# DOG.net
KiCad netlist of a schematic drawn in Altium Designer
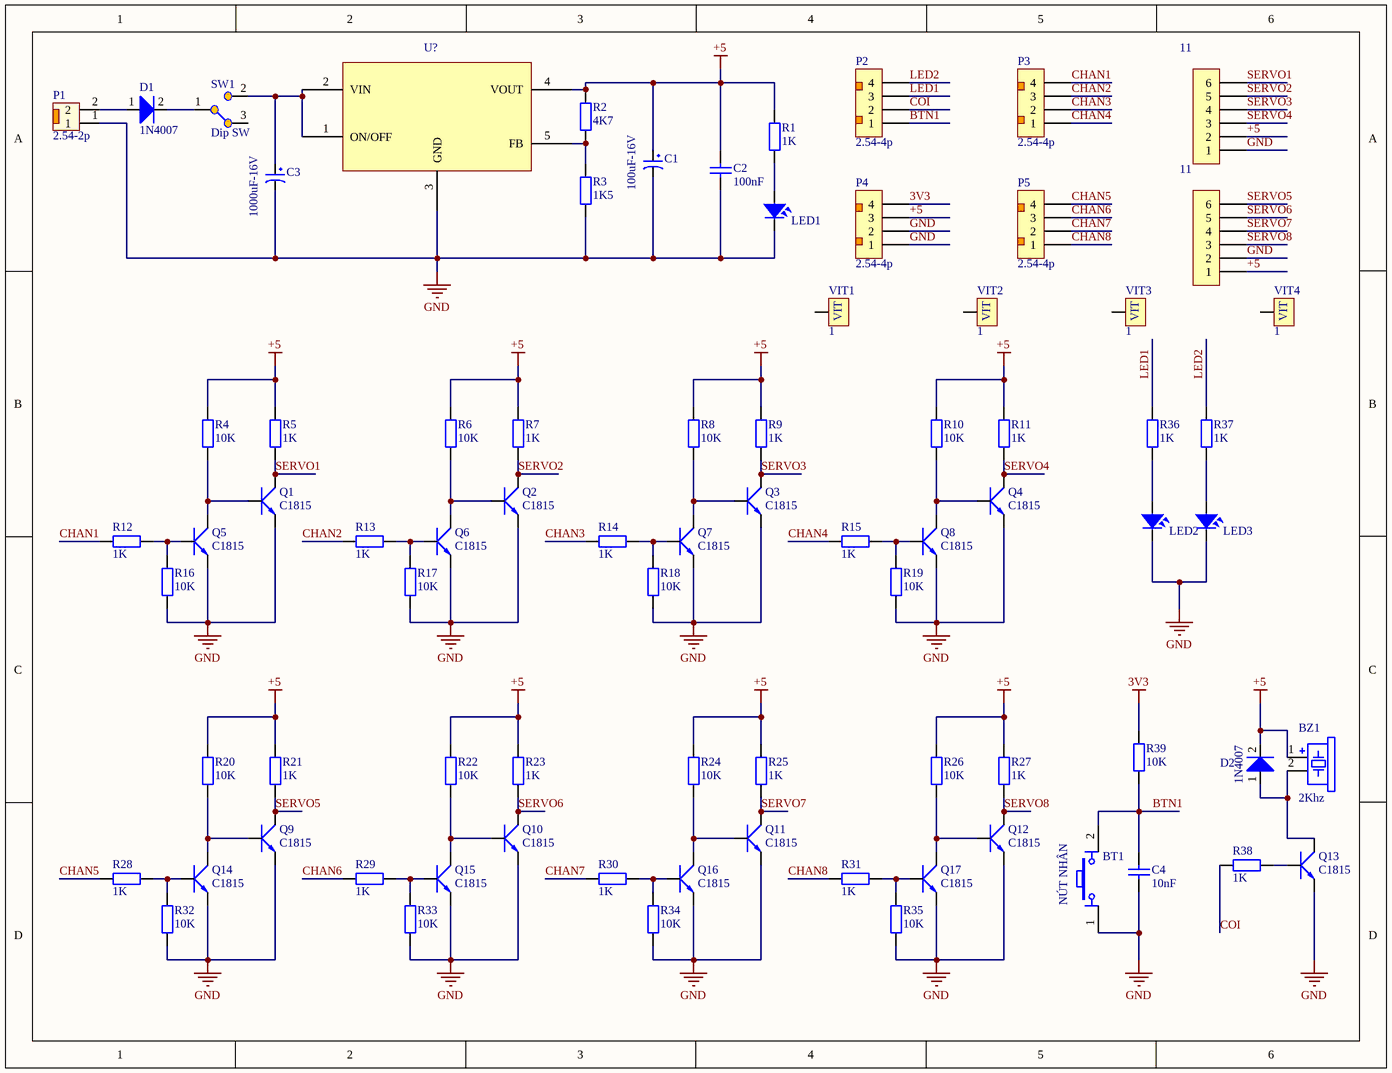
[diagram p0: DOG.SchDoc]

(export (version "E")
  (design (tool "Eeschema 10.0.6"))
  (components
    (comp (ref "BT1")
      (value "NÚT NHÂN")
      (footprint "Nut Nhan 4 Chan Cam 6x6")
      (description "Nut Nhan 4 Chan 6x6mm")
      (libsource (lib "Altium_Lib_by_KhueNguyenCreator") (part "Nut Nhan 4 Chan Cam 6x6"))
    )
    (comp (ref "BZ1")
      (value "2Khz")
      (footprint "coi xung")
      (description "Cắm")
      (libsource (lib "NhomLib") (part "Coi xung 2Khz"))
    )
    (comp (ref "C1")
      (value "100uF-16V")
      (footprint "tu hoa 5mm")
      (description "Cắm")
      (libsource (lib "NhomLib") (part "Tu Hoa 100uF 16V 5x7"))
    )
    (comp (ref "C2")
      (value "100nF")
      (footprint "tu gom")
      (description "Căm")
      (libsource (lib "NhomLib") (part "Tu gom 20pF 50V"))
    )
    (comp (ref "C3")
      (value "1000uF-16V")
      (footprint "tu hoa 8mm")
      (description "Cắm")
      (libsource (lib "NhomLib") (part "Tu Hoa 1000uF 16V 8x20"))
    )
    (comp (ref "C4")
      (value "10nF")
      (footprint "tu gom")
      (description "Căm")
      (libsource (lib "Altium_Lib_by_KhueNguyenCreator") (part "Tu gom 20pF 50V"))
    )
    (comp (ref "D1")
      (value "1N4007")
      (footprint "D5A")
      (description "Diode LS 1A 1000V DO-41")
      (libsource (lib "NhomLib") (part "1N4007"))
    )
    (comp (ref "D2")
      (value "1N4007")
      (footprint "1N4007")
      (description "Diode LS 1A 1000V DO-41")
      (libsource (lib "NhomLib") (part "1N4007"))
    )
    (comp (ref "H1")
      (value "11")
      (footprint "XH2.54M-6")
      (description "Cắm")
      (libsource (lib "Altium_Lib_by_KhueNguyenCreator") (part "Header 6P 2.54 Duc Thang"))
    )
    (comp (ref "H2")
      (value "11")
      (footprint "XH2.54M-6")
      (description "Cắm")
      (libsource (lib "Altium_Lib_by_KhueNguyenCreator") (part "Header 6P 2.54 Duc Thang"))
    )
    (comp (ref "LED1")
      (value "LED")
      (footprint "LED-5-RED")
      (description "LED Single colour Green and Red")
      (libsource (lib "NhomLib") (part "LED"))
    )
    (comp (ref "LED2")
      (value "LED")
      (footprint "LED-5-RED")
      (description "LED Single colour Green and Red")
      (libsource (lib "NhomLib") (part "LED"))
    )
    (comp (ref "LED3")
      (value "LED")
      (footprint "LED-5-Green")
      (description "LED Single colour Green and Red")
      (libsource (lib "NhomLib") (part "LED"))
    )
    (comp (ref "MIC1")
      (value "U?")
      (footprint "Mic5V")
      (description "3A")
      (libsource (lib "node_mcu") (part "Mic5V"))
    )
    (comp (ref "P1")
      (value "2.54-2p")
      (footprint "Header Duc Thang 2P 2.54")
      (description "Cắm")
      (libsource (lib "NhomLib") (part "Header 2.54-2p Duc Thang"))
    )
    (comp (ref "P2")
      (value "2.54-4p")
      (footprint "Header Duc Thang 4p 2.54")
      (description "Cắm")
      (libsource (lib "NhomLib") (part "Header 2.54_4p Duc Thang"))
    )
    (comp (ref "P3")
      (value "2.54-4p")
      (footprint "Header Duc Thang 4p 2.54")
      (description "Cắm")
      (libsource (lib "NhomLib") (part "Header 2.54_4p Duc Thang"))
    )
    (comp (ref "P4")
      (value "2.54-4p")
      (footprint "Header Duc Thang 4p 2.54")
      (description "Cắm")
      (libsource (lib "NhomLib") (part "Header 2.54_4p Duc Thang"))
    )
    (comp (ref "P5")
      (value "2.54-4p")
      (footprint "Header Duc Thang 4p 2.54")
      (description "Cắm")
      (libsource (lib "NhomLib") (part "Header 2.54_4p Duc Thang"))
    )
    (comp (ref "Q1")
      (value "C1815")
      (footprint "QTO-92")
      (description "NPN 600mW, ECB")
      (libsource (lib "syhaunguyen") (part "C1815"))
    )
    (comp (ref "Q2")
      (value "C1815")
      (footprint "QTO-92")
      (description "NPN 600mW, ECB")
      (libsource (lib "syhaunguyen") (part "C1815"))
    )
    (comp (ref "Q3")
      (value "C1815")
      (footprint "QTO-92")
      (description "NPN 600mW, ECB")
      (libsource (lib "syhaunguyen") (part "C1815"))
    )
    (comp (ref "Q4")
      (value "C1815")
      (footprint "QTO-92")
      (description "NPN 600mW, ECB")
      (libsource (lib "syhaunguyen") (part "C1815"))
    )
    (comp (ref "Q5")
      (value "C1815")
      (footprint "QTO-92")
      (description "NPN 600mW, ECB")
      (libsource (lib "syhaunguyen") (part "C1815"))
    )
    (comp (ref "Q6")
      (value "C1815")
      (footprint "QTO-92")
      (description "NPN 600mW, ECB")
      (libsource (lib "syhaunguyen") (part "C1815"))
    )
    (comp (ref "Q7")
      (value "C1815")
      (footprint "QTO-92")
      (description "NPN 600mW, ECB")
      (libsource (lib "syhaunguyen") (part "C1815"))
    )
    (comp (ref "Q8")
      (value "C1815")
      (footprint "QTO-92")
      (description "NPN 600mW, ECB")
      (libsource (lib "syhaunguyen") (part "C1815"))
    )
    (comp (ref "Q9")
      (value "C1815")
      (footprint "QTO-92")
      (description "NPN 600mW, ECB")
      (libsource (lib "syhaunguyen") (part "C1815"))
    )
    (comp (ref "Q10")
      (value "C1815")
      (footprint "QTO-92")
      (description "NPN 600mW, ECB")
      (libsource (lib "syhaunguyen") (part "C1815"))
    )
    (comp (ref "Q11")
      (value "C1815")
      (footprint "QTO-92")
      (description "NPN 600mW, ECB")
      (libsource (lib "syhaunguyen") (part "C1815"))
    )
    (comp (ref "Q12")
      (value "C1815")
      (footprint "QTO-92")
      (description "NPN 600mW, ECB")
      (libsource (lib "syhaunguyen") (part "C1815"))
    )
    (comp (ref "Q13")
      (value "C1815")
      (footprint "QTO-92")
      (description "NPN 600mW, ECB")
      (libsource (lib "syhaunguyen") (part "C1815"))
    )
    (comp (ref "Q14")
      (value "C1815")
      (footprint "QTO-92")
      (description "NPN 600mW, ECB")
      (libsource (lib "syhaunguyen") (part "C1815"))
    )
    (comp (ref "Q15")
      (value "C1815")
      (footprint "QTO-92")
      (description "NPN 600mW, ECB")
      (libsource (lib "syhaunguyen") (part "C1815"))
    )
    (comp (ref "Q16")
      (value "C1815")
      (footprint "QTO-92")
      (description "NPN 600mW, ECB")
      (libsource (lib "syhaunguyen") (part "C1815"))
    )
    (comp (ref "Q17")
      (value "C1815")
      (footprint "QTO-92")
      (description "NPN 600mW, ECB")
      (libsource (lib "syhaunguyen") (part "C1815"))
    )
    (comp (ref "R1")
      (value "1K")
      (footprint "tro vach 1/4w")
      (description "Cắm")
      (libsource (lib "NhomLib") (part "Tro Vach 1/4W 5% 1k"))
    )
    (comp (ref "R2")
      (value "4K7")
      (footprint "tro vach 1/4w")
      (description "Cắm")
      (libsource (lib "NhomLib") (part "Tro Vach 1/4W 5% 1k"))
    )
    (comp (ref "R3")
      (value "1K5")
      (footprint "tro vach 1/4w")
      (description "Cắm")
      (libsource (lib "NhomLib") (part "Tro Vach 1/4W 5% 1k"))
    )
    (comp (ref "R4")
      (value "10K")
      (footprint "tro vach 1/4w")
      (description "Cắm")
      (libsource (lib "NhomLib") (part "Tro Vach 1/4W 5% 1k"))
    )
    (comp (ref "R5")
      (value "1K")
      (footprint "tro vach 1/4w")
      (description "Cắm")
      (libsource (lib "NhomLib") (part "Tro Vach 1/4W 5% 1k"))
    )
    (comp (ref "R6")
      (value "10K")
      (footprint "tro vach 1/4w")
      (description "Cắm")
      (libsource (lib "NhomLib") (part "Tro Vach 1/4W 5% 1k"))
    )
    (comp (ref "R7")
      (value "1K")
      (footprint "tro vach 1/4w")
      (description "Cắm")
      (libsource (lib "NhomLib") (part "Tro Vach 1/4W 5% 1k"))
    )
    (comp (ref "R8")
      (value "10K")
      (footprint "tro vach 1/4w")
      (description "Cắm")
      (libsource (lib "NhomLib") (part "Tro Vach 1/4W 5% 1k"))
    )
    (comp (ref "R9")
      (value "1K")
      (footprint "tro vach 1/4w")
      (description "Cắm")
      (libsource (lib "NhomLib") (part "Tro Vach 1/4W 5% 1k"))
    )
    (comp (ref "R10")
      (value "10K")
      (footprint "tro vach 1/4w")
      (description "Cắm")
      (libsource (lib "NhomLib") (part "Tro Vach 1/4W 5% 1k"))
    )
    (comp (ref "R11")
      (value "1K")
      (footprint "tro vach 1/4w")
      (description "Cắm")
      (libsource (lib "NhomLib") (part "Tro Vach 1/4W 5% 1k"))
    )
    (comp (ref "R12")
      (value "1K")
      (footprint "tro vach 1/4w")
      (description "Cắm")
      (libsource (lib "NhomLib") (part "Tro Vach 1/4W 5% 1k"))
    )
    (comp (ref "R13")
      (value "1K")
      (footprint "tro vach 1/4w")
      (description "Cắm")
      (libsource (lib "NhomLib") (part "Tro Vach 1/4W 5% 1k"))
    )
    (comp (ref "R14")
      (value "1K")
      (footprint "tro vach 1/4w")
      (description "Cắm")
      (libsource (lib "NhomLib") (part "Tro Vach 1/4W 5% 1k"))
    )
    (comp (ref "R15")
      (value "1K")
      (footprint "tro vach 1/4w")
      (description "Cắm")
      (libsource (lib "NhomLib") (part "Tro Vach 1/4W 5% 1k"))
    )
    (comp (ref "R16")
      (value "10K")
      (footprint "tro vach 1/4w")
      (description "Cắm")
      (libsource (lib "NhomLib") (part "Tro Vach 1/4W 5% 1k"))
    )
    (comp (ref "R17")
      (value "10K")
      (footprint "tro vach 1/4w")
      (description "Cắm")
      (libsource (lib "NhomLib") (part "Tro Vach 1/4W 5% 1k"))
    )
    (comp (ref "R18")
      (value "10K")
      (footprint "tro vach 1/4w")
      (description "Cắm")
      (libsource (lib "NhomLib") (part "Tro Vach 1/4W 5% 1k"))
    )
    (comp (ref "R19")
      (value "10K")
      (footprint "tro vach 1/4w")
      (description "Cắm")
      (libsource (lib "NhomLib") (part "Tro Vach 1/4W 5% 1k"))
    )
    (comp (ref "R20")
      (value "10K")
      (footprint "tro vach 1/4w")
      (description "Cắm")
      (libsource (lib "NhomLib") (part "Tro Vach 1/4W 5% 1k"))
    )
    (comp (ref "R21")
      (value "1K")
      (footprint "tro vach 1/4w")
      (description "Cắm")
      (libsource (lib "NhomLib") (part "Tro Vach 1/4W 5% 1k"))
    )
    (comp (ref "R22")
      (value "10K")
      (footprint "tro vach 1/4w")
      (description "Cắm")
      (libsource (lib "NhomLib") (part "Tro Vach 1/4W 5% 1k"))
    )
    (comp (ref "R23")
      (value "1K")
      (footprint "tro vach 1/4w")
      (description "Cắm")
      (libsource (lib "NhomLib") (part "Tro Vach 1/4W 5% 1k"))
    )
    (comp (ref "R24")
      (value "10K")
      (footprint "tro vach 1/4w")
      (description "Cắm")
      (libsource (lib "NhomLib") (part "Tro Vach 1/4W 5% 1k"))
    )
    (comp (ref "R25")
      (value "1K")
      (footprint "tro vach 1/4w")
      (description "Cắm")
      (libsource (lib "NhomLib") (part "Tro Vach 1/4W 5% 1k"))
    )
    (comp (ref "R26")
      (value "10K")
      (footprint "tro vach 1/4w")
      (description "Cắm")
      (libsource (lib "NhomLib") (part "Tro Vach 1/4W 5% 1k"))
    )
    (comp (ref "R27")
      (value "1K")
      (footprint "tro vach 1/4w")
      (description "Cắm")
      (libsource (lib "NhomLib") (part "Tro Vach 1/4W 5% 1k"))
    )
    (comp (ref "R28")
      (value "1K")
      (footprint "tro vach 1/4w")
      (description "Cắm")
      (libsource (lib "NhomLib") (part "Tro Vach 1/4W 5% 1k"))
    )
    (comp (ref "R29")
      (value "1K")
      (footprint "tro vach 1/4w")
      (description "Cắm")
      (libsource (lib "NhomLib") (part "Tro Vach 1/4W 5% 1k"))
    )
    (comp (ref "R30")
      (value "1K")
      (footprint "tro vach 1/4w")
      (description "Cắm")
      (libsource (lib "NhomLib") (part "Tro Vach 1/4W 5% 1k"))
    )
    (comp (ref "R31")
      (value "1K")
      (footprint "tro vach 1/4w")
      (description "Cắm")
      (libsource (lib "NhomLib") (part "Tro Vach 1/4W 5% 1k"))
    )
    (comp (ref "R32")
      (value "10K")
      (footprint "tro vach 1/4w")
      (description "Cắm")
      (libsource (lib "NhomLib") (part "Tro Vach 1/4W 5% 1k"))
    )
    (comp (ref "R33")
      (value "10K")
      (footprint "tro vach 1/4w")
      (description "Cắm")
      (libsource (lib "NhomLib") (part "Tro Vach 1/4W 5% 1k"))
    )
    (comp (ref "R34")
      (value "10K")
      (footprint "tro vach 1/4w")
      (description "Cắm")
      (libsource (lib "NhomLib") (part "Tro Vach 1/4W 5% 1k"))
    )
    (comp (ref "R35")
      (value "10K")
      (footprint "tro vach 1/4w")
      (description "Cắm")
      (libsource (lib "NhomLib") (part "Tro Vach 1/4W 5% 1k"))
    )
    (comp (ref "R36")
      (value "1K")
      (footprint "tro vach 1/4w")
      (description "Cắm")
      (libsource (lib "NhomLib") (part "Tro Vach 1/4W 5% 1k"))
    )
    (comp (ref "R37")
      (value "1K")
      (footprint "tro vach 1/4w")
      (description "Cắm")
      (libsource (lib "NhomLib") (part "Tro Vach 1/4W 5% 1k"))
    )
    (comp (ref "R38")
      (value "1K")
      (footprint "tro vach 1/4w")
      (description "Cắm")
      (libsource (lib "NhomLib") (part "Tro Vach 1/4W 5% 1k"))
    )
    (comp (ref "R39")
      (value "10K")
      (footprint "tro vach 1/4w")
      (description "Cắm")
      (libsource (lib "NhomLib") (part "Tro Vach 1/4W 5% 1k"))
    )
    (comp (ref "SW1")
      (value "Dip SW")
      (footprint "SW3P")
      (description "Dip Switch 3 pin")
      (libsource (lib "VPMyLibrary") (part "Switch3P"))
    )
    (comp (ref "VIT1")
      (value "1")
      (footprint "VIT")
      (description "Oc Vit")
      (libsource (lib "NhomLib") (part "VIT"))
    )
    (comp (ref "VIT2")
      (value "1")
      (footprint "VIT")
      (description "Oc Vit")
      (libsource (lib "NhomLib") (part "VIT"))
    )
    (comp (ref "VIT3")
      (value "1")
      (footprint "VIT")
      (description "Oc Vit")
      (libsource (lib "NhomLib") (part "VIT"))
    )
    (comp (ref "VIT4")
      (value "1")
      (footprint "VIT")
      (description "Oc Vit")
      (libsource (lib "NhomLib") (part "VIT"))
    )
  )
  (nets
    (net (code "1") (name "+5") (class "Default")
      (node (ref "BZ1") (pin "1") (pinfunction "1_1") (pintype "passive"))
      (node (ref "C1") (pin "1") (pinfunction "1_1") (pintype "passive"))
      (node (ref "C2") (pin "1") (pinfunction "1_1") (pintype "passive"))
      (node (ref "D2") (pin "2") (pinfunction "K_2") (pintype "passive"))
      (node (ref "H1") (pin "2") (pinfunction "2_2") (pintype "passive"))
      (node (ref "H2") (pin "1") (pinfunction "1_1") (pintype "passive"))
      (node (ref "MIC1") (pin "4") (pinfunction "VOUT_4") (pintype "passive"))
      (node (ref "P4") (pin "3") (pinfunction "3_3") (pintype "passive"))
      (node (ref "R1") (pin "1") (pinfunction "1_1") (pintype "passive"))
      (node (ref "R10") (pin "2") (pinfunction "2_2") (pintype "passive"))
      (node (ref "R11") (pin "2") (pinfunction "2_2") (pintype "passive"))
      (node (ref "R2") (pin "2") (pinfunction "2_2") (pintype "passive"))
      (node (ref "R20") (pin "2") (pinfunction "2_2") (pintype "passive"))
      (node (ref "R21") (pin "2") (pinfunction "2_2") (pintype "passive"))
      (node (ref "R22") (pin "2") (pinfunction "2_2") (pintype "passive"))
      (node (ref "R23") (pin "2") (pinfunction "2_2") (pintype "passive"))
      (node (ref "R24") (pin "2") (pinfunction "2_2") (pintype "passive"))
      (node (ref "R25") (pin "2") (pinfunction "2_2") (pintype "passive"))
      (node (ref "R26") (pin "2") (pinfunction "2_2") (pintype "passive"))
      (node (ref "R27") (pin "2") (pinfunction "2_2") (pintype "passive"))
      (node (ref "R4") (pin "2") (pinfunction "2_2") (pintype "passive"))
      (node (ref "R5") (pin "2") (pinfunction "2_2") (pintype "passive"))
      (node (ref "R6") (pin "2") (pinfunction "2_2") (pintype "passive"))
      (node (ref "R7") (pin "2") (pinfunction "2_2") (pintype "passive"))
      (node (ref "R8") (pin "2") (pinfunction "2_2") (pintype "passive"))
      (node (ref "R9") (pin "2") (pinfunction "2_2") (pintype "passive"))
    )
    (net (code "2") (name "/BTN1") (class "Default")
      (node (ref "BT1") (pin "2") (pintype "passive"))
      (node (ref "C4") (pin "1") (pinfunction "1_1") (pintype "passive"))
      (node (ref "P2") (pin "1") (pinfunction "1_1") (pintype "passive"))
      (node (ref "R39") (pin "1") (pinfunction "1_1") (pintype "passive"))
    )
    (net (code "3") (name "/CHAN1") (class "Default")
      (node (ref "P3") (pin "4") (pinfunction "4_4") (pintype "passive"))
      (node (ref "R12") (pin "2") (pinfunction "2_2") (pintype "passive"))
    )
    (net (code "4") (name "/CHAN2") (class "Default")
      (node (ref "P3") (pin "3") (pinfunction "3_3") (pintype "passive"))
      (node (ref "R13") (pin "2") (pinfunction "2_2") (pintype "passive"))
    )
    (net (code "5") (name "/CHAN3") (class "Default")
      (node (ref "P3") (pin "2") (pinfunction "2_2") (pintype "passive"))
      (node (ref "R14") (pin "2") (pinfunction "2_2") (pintype "passive"))
    )
    (net (code "6") (name "/CHAN4") (class "Default")
      (node (ref "P3") (pin "1") (pinfunction "1_1") (pintype "passive"))
      (node (ref "R15") (pin "2") (pinfunction "2_2") (pintype "passive"))
    )
    (net (code "7") (name "/CHAN5") (class "Default")
      (node (ref "P5") (pin "4") (pinfunction "4_4") (pintype "passive"))
      (node (ref "R28") (pin "2") (pinfunction "2_2") (pintype "passive"))
    )
    (net (code "8") (name "/CHAN6") (class "Default")
      (node (ref "P5") (pin "3") (pinfunction "3_3") (pintype "passive"))
      (node (ref "R29") (pin "2") (pinfunction "2_2") (pintype "passive"))
    )
    (net (code "9") (name "/CHAN7") (class "Default")
      (node (ref "P5") (pin "2") (pinfunction "2_2") (pintype "passive"))
      (node (ref "R30") (pin "2") (pinfunction "2_2") (pintype "passive"))
    )
    (net (code "10") (name "/CHAN8") (class "Default")
      (node (ref "P5") (pin "1") (pinfunction "1_1") (pintype "passive"))
      (node (ref "R31") (pin "2") (pinfunction "2_2") (pintype "passive"))
    )
    (net (code "11") (name "/COI") (class "Default")
      (node (ref "P2") (pin "2") (pinfunction "2_2") (pintype "passive"))
      (node (ref "R38") (pin "2") (pinfunction "2_2") (pintype "passive"))
    )
    (net (code "12") (name "/LED1") (class "Default")
      (node (ref "P2") (pin "3") (pinfunction "3_3") (pintype "passive"))
      (node (ref "R36") (pin "1") (pinfunction "1_1") (pintype "passive"))
    )
    (net (code "13") (name "/LED2") (class "Default")
      (node (ref "P2") (pin "4") (pinfunction "4_4") (pintype "passive"))
      (node (ref "R37") (pin "1") (pinfunction "1_1") (pintype "passive"))
    )
    (net (code "14") (name "/SERVO1") (class "Default")
      (node (ref "H1") (pin "6") (pinfunction "6_6") (pintype "passive"))
      (node (ref "Q1") (pin "2") (pinfunction "C_2") (pintype "passive"))
      (node (ref "R5") (pin "1") (pinfunction "1_1") (pintype "passive"))
    )
    (net (code "15") (name "/SERVO2") (class "Default")
      (node (ref "H1") (pin "5") (pinfunction "5_5") (pintype "passive"))
      (node (ref "Q2") (pin "2") (pinfunction "C_2") (pintype "passive"))
      (node (ref "R7") (pin "1") (pinfunction "1_1") (pintype "passive"))
    )
    (net (code "16") (name "/SERVO3") (class "Default")
      (node (ref "H1") (pin "4") (pinfunction "4_4") (pintype "passive"))
      (node (ref "Q3") (pin "2") (pinfunction "C_2") (pintype "passive"))
      (node (ref "R9") (pin "1") (pinfunction "1_1") (pintype "passive"))
    )
    (net (code "17") (name "/SERVO4") (class "Default")
      (node (ref "H1") (pin "3") (pinfunction "3_3") (pintype "passive"))
      (node (ref "Q4") (pin "2") (pinfunction "C_2") (pintype "passive"))
      (node (ref "R11") (pin "1") (pinfunction "1_1") (pintype "passive"))
    )
    (net (code "18") (name "/SERVO5") (class "Default")
      (node (ref "H2") (pin "6") (pinfunction "6_6") (pintype "passive"))
      (node (ref "Q9") (pin "2") (pinfunction "C_2") (pintype "passive"))
      (node (ref "R21") (pin "1") (pinfunction "1_1") (pintype "passive"))
    )
    (net (code "19") (name "/SERVO6") (class "Default")
      (node (ref "H2") (pin "5") (pinfunction "5_5") (pintype "passive"))
      (node (ref "Q10") (pin "2") (pinfunction "C_2") (pintype "passive"))
      (node (ref "R23") (pin "1") (pinfunction "1_1") (pintype "passive"))
    )
    (net (code "20") (name "/SERVO7") (class "Default")
      (node (ref "H2") (pin "4") (pinfunction "4_4") (pintype "passive"))
      (node (ref "Q11") (pin "2") (pinfunction "C_2") (pintype "passive"))
      (node (ref "R25") (pin "1") (pinfunction "1_1") (pintype "passive"))
    )
    (net (code "21") (name "/SERVO8") (class "Default")
      (node (ref "H2") (pin "3") (pinfunction "3_3") (pintype "passive"))
      (node (ref "Q12") (pin "2") (pinfunction "C_2") (pintype "passive"))
      (node (ref "R27") (pin "1") (pinfunction "1_1") (pintype "passive"))
    )
    (net (code "22") (name "3V3") (class "Default")
      (node (ref "P4") (pin "4") (pinfunction "4_4") (pintype "passive"))
      (node (ref "R39") (pin "2") (pinfunction "2_2") (pintype "passive"))
    )
    (net (code "23") (name "GND") (class "Default")
      (node (ref "BT1") (pin "1") (pintype "passive"))
      (node (ref "C1") (pin "2") (pinfunction "2_2") (pintype "passive"))
      (node (ref "C2") (pin "2") (pinfunction "2_2") (pintype "passive"))
      (node (ref "C3") (pin "2") (pinfunction "2_2") (pintype "passive"))
      (node (ref "C4") (pin "2") (pinfunction "2_2") (pintype "passive"))
      (node (ref "H1") (pin "1") (pinfunction "1_1") (pintype "passive"))
      (node (ref "H2") (pin "2") (pinfunction "2_2") (pintype "passive"))
      (node (ref "LED1") (pin "2") (pinfunction "2_2") (pintype "passive"))
      (node (ref "LED2") (pin "2") (pinfunction "2_2") (pintype "passive"))
      (node (ref "LED3") (pin "2") (pinfunction "2_2") (pintype "passive"))
      (node (ref "MIC1") (pin "3") (pinfunction "GND_3") (pintype "passive"))
      (node (ref "P1") (pin "1") (pinfunction "1_1") (pintype "passive"))
      (node (ref "P4") (pin "1") (pinfunction "1_1") (pintype "passive"))
      (node (ref "P4") (pin "2") (pinfunction "2_2") (pintype "passive"))
      (node (ref "Q1") (pin "1") (pinfunction "E_1") (pintype "passive"))
      (node (ref "Q10") (pin "1") (pinfunction "E_1") (pintype "passive"))
      (node (ref "Q11") (pin "1") (pinfunction "E_1") (pintype "passive"))
      (node (ref "Q12") (pin "1") (pinfunction "E_1") (pintype "passive"))
      (node (ref "Q13") (pin "1") (pinfunction "E_1") (pintype "passive"))
      (node (ref "Q14") (pin "1") (pinfunction "E_1") (pintype "passive"))
      (node (ref "Q15") (pin "1") (pinfunction "E_1") (pintype "passive"))
      (node (ref "Q16") (pin "1") (pinfunction "E_1") (pintype "passive"))
      (node (ref "Q17") (pin "1") (pinfunction "E_1") (pintype "passive"))
      (node (ref "Q2") (pin "1") (pinfunction "E_1") (pintype "passive"))
      (node (ref "Q3") (pin "1") (pinfunction "E_1") (pintype "passive"))
      (node (ref "Q4") (pin "1") (pinfunction "E_1") (pintype "passive"))
      (node (ref "Q5") (pin "1") (pinfunction "E_1") (pintype "passive"))
      (node (ref "Q6") (pin "1") (pinfunction "E_1") (pintype "passive"))
      (node (ref "Q7") (pin "1") (pinfunction "E_1") (pintype "passive"))
      (node (ref "Q8") (pin "1") (pinfunction "E_1") (pintype "passive"))
      (node (ref "Q9") (pin "1") (pinfunction "E_1") (pintype "passive"))
      (node (ref "R16") (pin "1") (pinfunction "1_1") (pintype "passive"))
      (node (ref "R17") (pin "1") (pinfunction "1_1") (pintype "passive"))
      (node (ref "R18") (pin "1") (pinfunction "1_1") (pintype "passive"))
      (node (ref "R19") (pin "1") (pinfunction "1_1") (pintype "passive"))
      (node (ref "R3") (pin "1") (pinfunction "1_1") (pintype "passive"))
      (node (ref "R32") (pin "1") (pinfunction "1_1") (pintype "passive"))
      (node (ref "R33") (pin "1") (pinfunction "1_1") (pintype "passive"))
      (node (ref "R34") (pin "1") (pinfunction "1_1") (pintype "passive"))
      (node (ref "R35") (pin "1") (pinfunction "1_1") (pintype "passive"))
    )
    (net (code "24") (name "Net-(D1-A)") (class "Default")
      (node (ref "D1") (pin "1") (pinfunction "A_1") (pintype "passive"))
      (node (ref "P1") (pin "2") (pinfunction "2_2") (pintype "passive"))
    )
    (net (code "25") (name "Net-(D1-K)") (class "Default")
      (node (ref "D1") (pin "2") (pinfunction "K_2") (pintype "passive"))
      (node (ref "SW1") (pin "1") (pinfunction "COM_1") (pintype "passive"))
    )
    (net (code "26") (name "Net-(D2-A)") (class "Default")
      (node (ref "BZ1") (pin "2") (pinfunction "2_2") (pintype "passive"))
      (node (ref "D2") (pin "1") (pinfunction "A_1") (pintype "passive"))
      (node (ref "Q13") (pin "2") (pinfunction "C_2") (pintype "passive"))
    )
    (net (code "27") (name "Net-(LED1-Pad1)") (class "Default")
      (node (ref "LED1") (pin "1") (pinfunction "1_1") (pintype "passive"))
      (node (ref "R1") (pin "2") (pinfunction "2_2") (pintype "passive"))
    )
    (net (code "28") (name "Net-(LED2-Pad1)") (class "Default")
      (node (ref "LED2") (pin "1") (pinfunction "1_1") (pintype "passive"))
      (node (ref "R36") (pin "2") (pinfunction "2_2") (pintype "passive"))
    )
    (net (code "29") (name "Net-(LED3-Pad1)") (class "Default")
      (node (ref "LED3") (pin "1") (pinfunction "1_1") (pintype "passive"))
      (node (ref "R37") (pin "2") (pinfunction "2_2") (pintype "passive"))
    )
    (net (code "30") (name "Net-(MIC1-FB)") (class "Default")
      (node (ref "MIC1") (pin "5") (pinfunction "FB_5") (pintype "passive"))
      (node (ref "R2") (pin "1") (pinfunction "1_1") (pintype "passive"))
      (node (ref "R3") (pin "2") (pinfunction "2_2") (pintype "passive"))
    )
    (net (code "31") (name "Net-(MIC1-ON{slash}OFF)") (class "Default")
      (node (ref "C3") (pin "1") (pinfunction "1_1") (pintype "passive"))
      (node (ref "MIC1") (pin "1") (pinfunction "ON/OFF_1") (pintype "passive"))
      (node (ref "MIC1") (pin "2") (pinfunction "VIN_2") (pintype "passive"))
      (node (ref "SW1") (pin "2") (pinfunction "NC_2") (pintype "passive"))
    )
    (net (code "32") (name "Net-(Q1-B)") (class "Default")
      (node (ref "Q1") (pin "3") (pinfunction "B_3") (pintype "passive"))
      (node (ref "Q5") (pin "2") (pinfunction "C_2") (pintype "passive"))
      (node (ref "R4") (pin "1") (pinfunction "1_1") (pintype "passive"))
    )
    (net (code "33") (name "Net-(Q2-B)") (class "Default")
      (node (ref "Q2") (pin "3") (pinfunction "B_3") (pintype "passive"))
      (node (ref "Q6") (pin "2") (pinfunction "C_2") (pintype "passive"))
      (node (ref "R6") (pin "1") (pinfunction "1_1") (pintype "passive"))
    )
    (net (code "34") (name "Net-(Q3-B)") (class "Default")
      (node (ref "Q3") (pin "3") (pinfunction "B_3") (pintype "passive"))
      (node (ref "Q7") (pin "2") (pinfunction "C_2") (pintype "passive"))
      (node (ref "R8") (pin "1") (pinfunction "1_1") (pintype "passive"))
    )
    (net (code "35") (name "Net-(Q4-B)") (class "Default")
      (node (ref "Q4") (pin "3") (pinfunction "B_3") (pintype "passive"))
      (node (ref "Q8") (pin "2") (pinfunction "C_2") (pintype "passive"))
      (node (ref "R10") (pin "1") (pinfunction "1_1") (pintype "passive"))
    )
    (net (code "36") (name "Net-(Q5-B)") (class "Default")
      (node (ref "Q5") (pin "3") (pinfunction "B_3") (pintype "passive"))
      (node (ref "R12") (pin "1") (pinfunction "1_1") (pintype "passive"))
      (node (ref "R16") (pin "2") (pinfunction "2_2") (pintype "passive"))
    )
    (net (code "37") (name "Net-(Q6-B)") (class "Default")
      (node (ref "Q6") (pin "3") (pinfunction "B_3") (pintype "passive"))
      (node (ref "R13") (pin "1") (pinfunction "1_1") (pintype "passive"))
      (node (ref "R17") (pin "2") (pinfunction "2_2") (pintype "passive"))
    )
    (net (code "38") (name "Net-(Q7-B)") (class "Default")
      (node (ref "Q7") (pin "3") (pinfunction "B_3") (pintype "passive"))
      (node (ref "R14") (pin "1") (pinfunction "1_1") (pintype "passive"))
      (node (ref "R18") (pin "2") (pinfunction "2_2") (pintype "passive"))
    )
    (net (code "39") (name "Net-(Q8-B)") (class "Default")
      (node (ref "Q8") (pin "3") (pinfunction "B_3") (pintype "passive"))
      (node (ref "R15") (pin "1") (pinfunction "1_1") (pintype "passive"))
      (node (ref "R19") (pin "2") (pinfunction "2_2") (pintype "passive"))
    )
    (net (code "40") (name "Net-(Q10-B)") (class "Default")
      (node (ref "Q10") (pin "3") (pinfunction "B_3") (pintype "passive"))
      (node (ref "Q15") (pin "2") (pinfunction "C_2") (pintype "passive"))
      (node (ref "R22") (pin "1") (pinfunction "1_1") (pintype "passive"))
    )
    (net (code "41") (name "Net-(Q11-B)") (class "Default")
      (node (ref "Q11") (pin "3") (pinfunction "B_3") (pintype "passive"))
      (node (ref "Q16") (pin "2") (pinfunction "C_2") (pintype "passive"))
      (node (ref "R24") (pin "1") (pinfunction "1_1") (pintype "passive"))
    )
    (net (code "42") (name "Net-(Q12-B)") (class "Default")
      (node (ref "Q12") (pin "3") (pinfunction "B_3") (pintype "passive"))
      (node (ref "Q17") (pin "2") (pinfunction "C_2") (pintype "passive"))
      (node (ref "R26") (pin "1") (pinfunction "1_1") (pintype "passive"))
    )
    (net (code "43") (name "Net-(Q13-B)") (class "Default")
      (node (ref "Q13") (pin "3") (pinfunction "B_3") (pintype "passive"))
      (node (ref "R38") (pin "1") (pinfunction "1_1") (pintype "passive"))
    )
    (net (code "44") (name "Net-(Q14-B)") (class "Default")
      (node (ref "Q14") (pin "3") (pinfunction "B_3") (pintype "passive"))
      (node (ref "R28") (pin "1") (pinfunction "1_1") (pintype "passive"))
      (node (ref "R32") (pin "2") (pinfunction "2_2") (pintype "passive"))
    )
    (net (code "45") (name "Net-(Q14-C)") (class "Default")
      (node (ref "Q14") (pin "2") (pinfunction "C_2") (pintype "passive"))
      (node (ref "Q9") (pin "3") (pinfunction "B_3") (pintype "passive"))
      (node (ref "R20") (pin "1") (pinfunction "1_1") (pintype "passive"))
    )
    (net (code "46") (name "Net-(Q15-B)") (class "Default")
      (node (ref "Q15") (pin "3") (pinfunction "B_3") (pintype "passive"))
      (node (ref "R29") (pin "1") (pinfunction "1_1") (pintype "passive"))
      (node (ref "R33") (pin "2") (pinfunction "2_2") (pintype "passive"))
    )
    (net (code "47") (name "Net-(Q16-B)") (class "Default")
      (node (ref "Q16") (pin "3") (pinfunction "B_3") (pintype "passive"))
      (node (ref "R30") (pin "1") (pinfunction "1_1") (pintype "passive"))
      (node (ref "R34") (pin "2") (pinfunction "2_2") (pintype "passive"))
    )
    (net (code "48") (name "Net-(Q17-B)") (class "Default")
      (node (ref "Q17") (pin "3") (pinfunction "B_3") (pintype "passive"))
      (node (ref "R31") (pin "1") (pinfunction "1_1") (pintype "passive"))
      (node (ref "R35") (pin "2") (pinfunction "2_2") (pintype "passive"))
    )
    (net (code "49") (name "unconnected-(SW1-NO-Pad3)") (class "Default")
      (node (ref "SW1") (pin "3") (pinfunction "NO_3") (pintype "passive"))
    )
    (net (code "50") (name "unconnected-(VIT1-1-PadVIT1)") (class "Default")
      (node (ref "VIT1") (pin "VIT1") (pinfunction "1_VIT1") (pintype "passive"))
    )
    (net (code "51") (name "unconnected-(VIT2-1-PadVIT1)") (class "Default")
      (node (ref "VIT2") (pin "VIT1") (pinfunction "1_VIT1") (pintype "passive"))
    )
    (net (code "52") (name "unconnected-(VIT3-1-PadVIT1)") (class "Default")
      (node (ref "VIT3") (pin "VIT1") (pinfunction "1_VIT1") (pintype "passive"))
    )
    (net (code "53") (name "unconnected-(VIT4-1-PadVIT1)") (class "Default")
      (node (ref "VIT4") (pin "VIT1") (pinfunction "1_VIT1") (pintype "passive"))
    )
  )
)
